# untitled.net
KiCad netlist of a schematic drawn in EAGLE
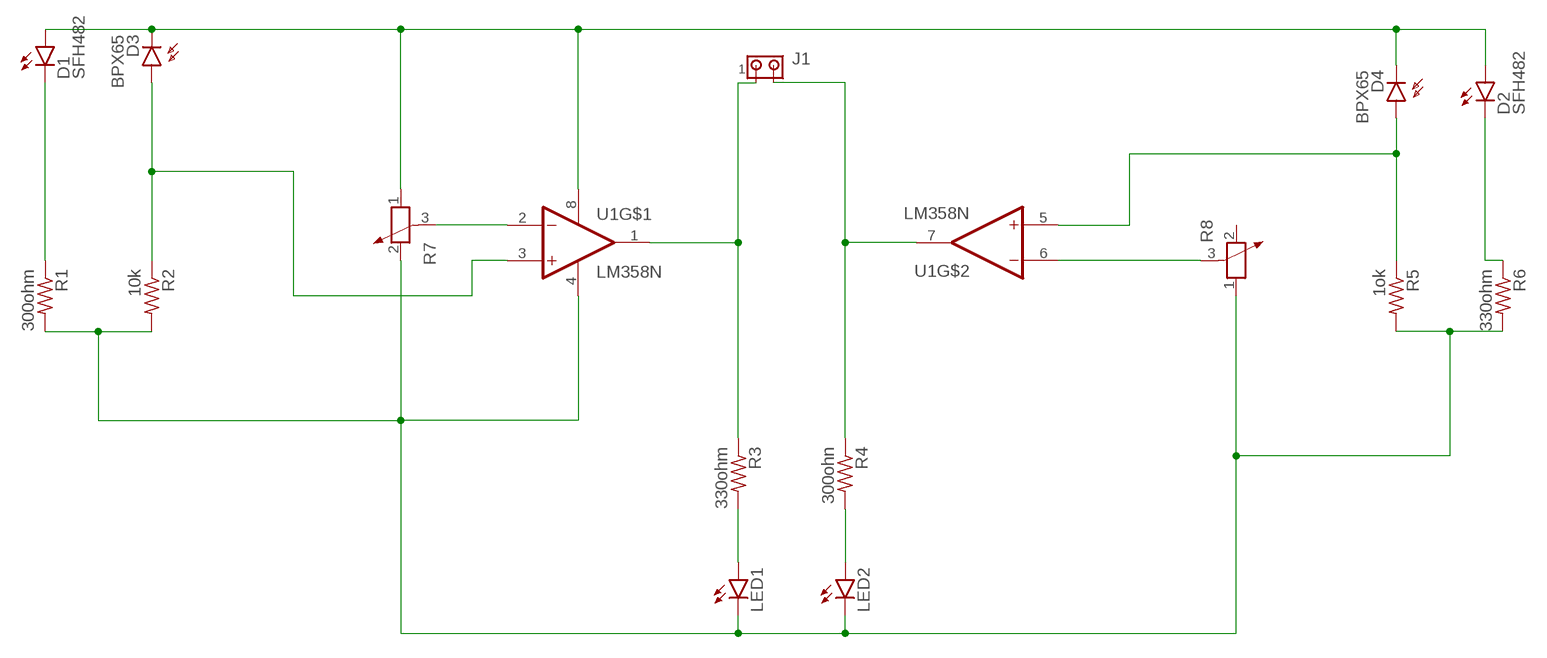
[diagram p0: schematic, sheet 1]

(export (version "E")
  (design (tool "Eeschema 10.0.6"))
  (components
    (comp (ref "D1")
      (value "SFH482")
      (footprint "eagle-import:SFH482")
      (libsource (lib "eagle-import") (part "SFH482"))
    )
    (comp (ref "D2")
      (value "SFH482")
      (footprint "eagle-import:SFH482")
      (libsource (lib "eagle-import") (part "SFH482"))
    )
    (comp (ref "D3")
      (value "BPX65")
      (footprint "eagle-import:BPX65")
      (fields (field (name "MPN") "BPX65."))
      (libsource (lib "eagle-import") (part "BPX65"))
    )
    (comp (ref "D4")
      (value "BPX65")
      (footprint "eagle-import:BPX65")
      (fields (field (name "MPN") "BPX65."))
      (libsource (lib "eagle-import") (part "BPX65"))
    )
    (comp (ref "J1")
      (value "MTA02-100")
      (footprint "eagle-import:10X02MTA")
      (libsource (lib "eagle-import") (part "MTA02-100"))
    )
    (comp (ref "LED1")
      (value "LED3MM")
      (footprint "eagle-import:LED3MM")
      (libsource (lib "eagle-import") (part "LED3MM"))
    )
    (comp (ref "LED2")
      (value "LED3MM")
      (footprint "eagle-import:LED3MM")
      (libsource (lib "eagle-import") (part "LED3MM"))
    )
    (comp (ref "R1")
      (value "300ohm")
      (footprint "eagle-import:0204_5")
      (libsource (lib "eagle-import") (part "R-US_0204/5"))
    )
    (comp (ref "R2")
      (value "10k")
      (footprint "eagle-import:0204_5")
      (libsource (lib "eagle-import") (part "R-US_0204/5"))
    )
    (comp (ref "R3")
      (value "330ohm")
      (footprint "eagle-import:0204_5")
      (libsource (lib "eagle-import") (part "R-US_0204/5"))
    )
    (comp (ref "R4")
      (value "300ohn")
      (footprint "eagle-import:0204_5")
      (libsource (lib "eagle-import") (part "R-US_0204/5"))
    )
    (comp (ref "R5")
      (value "1ok")
      (footprint "eagle-import:0204_5")
      (libsource (lib "eagle-import") (part "R-US_0204/5"))
    )
    (comp (ref "R6")
      (value "330ohm")
      (footprint "eagle-import:0204_5")
      (libsource (lib "eagle-import") (part "R-US_0204/5"))
    )
    (comp (ref "R7")
      (value "POTENTIOMETER_PT-10")
      (footprint "eagle-import:PT-10")
      (libsource (lib "eagle-import") (part "POTENTIOMETER_PT-10"))
    )
    (comp (ref "R8")
      (value "POTENTIOMETER_PT-10")
      (footprint "eagle-import:PT-10")
      (libsource (lib "eagle-import") (part "POTENTIOMETER_PT-10"))
    )
    (comp (ref "U1")
      (value "LM358N")
      (footprint "eagle-import:DIP762W46P254L960H508Q8")
      (fields (field (name "MF") "Harris Corporation"))
      (libsource (lib "eagle-import") (part "LM358N"))
    )
  )
  (nets
    (net (code "1") (name "Net-(D1-C)") (class "Default")
      (node (ref "D1") (pin "K") (pinfunction "C_K") (pintype "passive"))
      (node (ref "R1") (pin "1") (pinfunction "1_1") (pintype "passive"))
    )
    (net (code "2") (name "Net-(D2-C)") (class "Default")
      (node (ref "D2") (pin "K") (pinfunction "C_K") (pintype "passive"))
      (node (ref "R6") (pin "1") (pinfunction "1_1") (pintype "passive"))
    )
    (net (code "3") (name "Net-(D3-C)") (class "Default")
      (node (ref "D1") (pin "A") (pinfunction "A_A") (pintype "passive"))
      (node (ref "D2") (pin "A") (pinfunction "A_A") (pintype "passive"))
      (node (ref "D3") (pin "K") (pinfunction "C_K") (pintype "passive"))
      (node (ref "D4") (pin "K") (pinfunction "C_K") (pintype "passive"))
      (node (ref "R7") (pin "1") (pinfunction "1_1") (pintype "passive"))
      (node (ref "U1") (pin "8") (pinfunction "VCC_8") (pintype "power_in"))
    )
    (net (code "4") (name "Net-(LED1-C)") (class "Default")
      (node (ref "LED1") (pin "K") (pinfunction "C_K") (pintype "passive"))
      (node (ref "LED2") (pin "K") (pinfunction "C_K") (pintype "passive"))
      (node (ref "R1") (pin "2") (pinfunction "2_2") (pintype "passive"))
      (node (ref "R2") (pin "2") (pinfunction "2_2") (pintype "passive"))
      (node (ref "R5") (pin "2") (pinfunction "2_2") (pintype "passive"))
      (node (ref "R6") (pin "2") (pinfunction "2_2") (pintype "passive"))
      (node (ref "R7") (pin "2") (pinfunction "2_2") (pintype "passive"))
      (node (ref "R8") (pin "1") (pinfunction "1_1") (pintype "passive"))
      (node (ref "U1") (pin "4") (pinfunction "GND_4") (pintype "power_in"))
    )
    (net (code "5") (name "Net-(LED1-PadA)") (class "Default")
      (node (ref "LED1") (pin "A") (pinfunction "A_A") (pintype "passive"))
      (node (ref "R3") (pin "2") (pinfunction "2_2") (pintype "passive"))
    )
    (net (code "6") (name "Net-(LED2-PadA)") (class "Default")
      (node (ref "LED2") (pin "A") (pinfunction "A_A") (pintype "passive"))
      (node (ref "R4") (pin "2") (pinfunction "2_2") (pintype "passive"))
    )
    (net (code "7") (name "Net-(U1A-1IN+)") (class "Default")
      (node (ref "D3") (pin "A") (pinfunction "A_A") (pintype "passive"))
      (node (ref "R2") (pin "1") (pinfunction "1_1") (pintype "passive"))
      (node (ref "U1") (pin "3") (pinfunction "1IN+_3") (pintype "input"))
    )
    (net (code "8") (name "Net-(U1A-1IN-)") (class "Default")
      (node (ref "R7") (pin "3") (pinfunction "3_3") (pintype "passive"))
      (node (ref "U1") (pin "2") (pinfunction "1IN-_2") (pintype "input"))
    )
    (net (code "9") (name "Net-(U1A-1OUT)") (class "Default")
      (node (ref "J1") (pin "1") (pinfunction "1_1") (pintype "passive"))
      (node (ref "R3") (pin "1") (pinfunction "1_1") (pintype "passive"))
      (node (ref "U1") (pin "1") (pinfunction "1OUT_1") (pintype "output"))
    )
    (net (code "10") (name "Net-(U1B-2IN+)") (class "Default")
      (node (ref "D4") (pin "A") (pinfunction "A_A") (pintype "passive"))
      (node (ref "R5") (pin "1") (pinfunction "1_1") (pintype "passive"))
      (node (ref "U1") (pin "5") (pinfunction "2IN+_5") (pintype "input"))
    )
    (net (code "11") (name "Net-(U1B-2IN-)") (class "Default")
      (node (ref "R8") (pin "3") (pinfunction "3_3") (pintype "passive"))
      (node (ref "U1") (pin "6") (pinfunction "2IN-_6") (pintype "input"))
    )
    (net (code "12") (name "Net-(U1B-2OUT)") (class "Default")
      (node (ref "J1") (pin "2") (pinfunction "2_2") (pintype "passive"))
      (node (ref "R4") (pin "1") (pinfunction "1_1") (pintype "passive"))
      (node (ref "U1") (pin "7") (pinfunction "2OUT_7") (pintype "output"))
    )
    (net (code "13") (name "unconnected-(R8-Pad2)") (class "Default")
      (node (ref "R8") (pin "2") (pinfunction "2_2") (pintype "passive"))
    )
  )
)
